# LHC_Power.net
KiCad netlist of a schematic drawn in Altium Designer
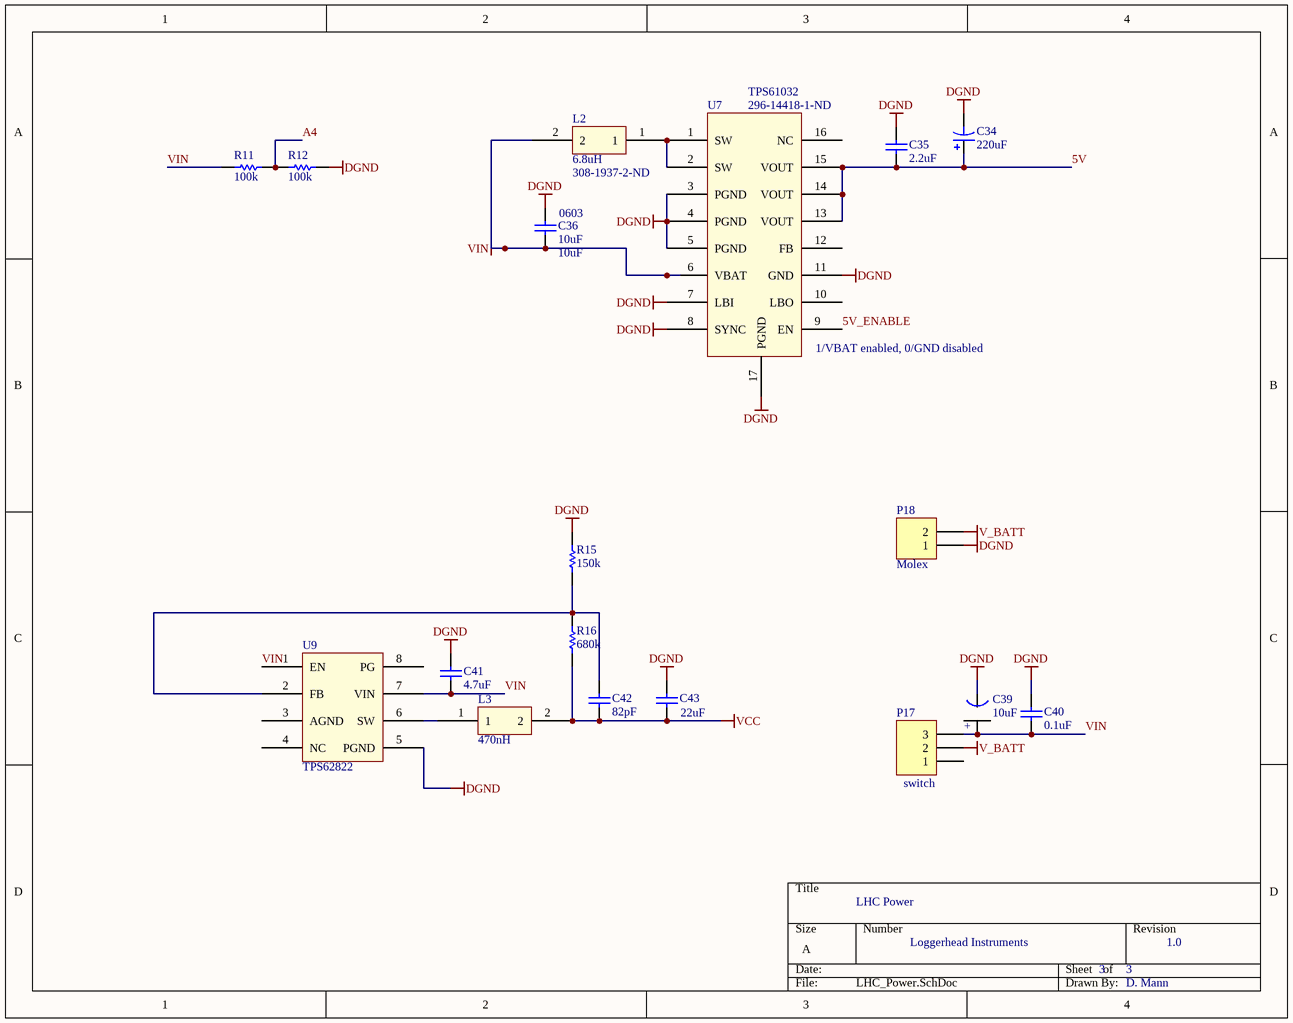
[diagram p0: LHC_Power.SchDoc]

(export (version "E")
  (design (tool "Eeschema 10.0.6"))
  (components
    (comp (ref "C34")
      (value "220uF")
      (footprint "X")
      (description "Solid Tantalum Chip Capacitor, Standard T495 Series - Low ESR, Surge Robust")
      (fields (field (name "PUBLISHER") "Altium Limited"))
      (libsource (lib "KEMET Chip Capacitor") (part "T495X"))
    )
    (comp (ref "C35")
      (value "2.2uF")
      (footprint "0402")
      (description "Ceramic Chip Capacitor - Standard")
      (fields (field (name "PUBLISHER") "Altium Limited"))
      (libsource (lib "KEMET Chip Capacitor") (part "C0402"))
    )
    (comp (ref "C36")
      (value "10uF")
      (footprint "0603")
      (description "Ceramic Chip Capacitor - 0603")
      (fields
        (field (name "PACKAGEREFERENCE") "0603")
        (field (name "ALTIUM_VALUE") "10uF")
        (field (name "PUBLISHER") "Altium Limited")
      )
      (libsource (lib "KEMET Chip Capacitor") (part "C0603"))
    )
    (comp (ref "C39") (value "10uF") (footprint "Tant0805") (libsource (lib "Loggerhead") (part "Tant0805")))
    (comp (ref "C40")
      (value "0.1uF")
      (footprint "0402")
      (description "Ceramic Chip Capacitor - Standard")
      (fields (field (name "PUBLISHER") "Altium Limited"))
      (libsource (lib "KEMET Chip Capacitor") (part "C0402"))
    )
    (comp (ref "C41")
      (value "4.7uF")
      (footprint "0603")
      (description "Ceramic Chip Capacitor - Standard")
      (fields (field (name "PUBLISHER") "Altium Limited"))
      (libsource (lib "KEMET Chip Capacitor") (part "C0603"))
    )
    (comp (ref "C42")
      (value "82pF")
      (footprint "0402")
      (description "Ceramic Chip Capacitor - Standard")
      (fields (field (name "PUBLISHER") "Altium Limited"))
      (libsource (lib "KEMET Chip Capacitor") (part "C0402"))
    )
    (comp (ref "C43")
      (value "22uF")
      (footprint "0603")
      (description "Ceramic Chip Capacitor - Standard")
      (fields (field (name "PUBLISHER") "Altium Limited"))
      (libsource (lib "KEMET Chip Capacitor") (part "C0603"))
    )
    (comp (ref "L2")
      (value "6.8uH")
      (footprint "Inductor - duplicate")
      (description "Sumida Inductor")
      (fields (field (name "SUPPLIER PART NUMBER 1") "308-1937-2-ND"))
      (libsource (lib "Loggerhead") (part "Inductor 6.8uH"))
    )
    (comp (ref "L3")
      (value "470nH")
      (footprint "Inductor_470NH")
      (libsource (lib "Loggerhead") (part "Inductor_470NH"))
    )
    (comp (ref "P17")
      (value "switch")
      (footprint "HDR1X3")
      (description "Header, 3-Pin")
      (fields (field (name "PUBLISHER") "Altium Limited"))
      (libsource (lib "Miscellaneous Connectors") (part "Header 3"))
    )
    (comp (ref "P18")
      (value "Molex")
      (footprint "HDR1X2")
      (description "Header, 2-Pin")
      (fields (field (name "PUBLISHER") "Altium Limited"))
      (libsource (lib "Miscellaneous Connectors") (part "Header 2"))
    )
    (comp (ref "R11")
      (value "100k")
      (footprint "3-0603")
      (fields (field (name "PUBLISHER") "Altium Limited"))
      (libsource (lib "Panasonic Resistor") (part "ERJ3RK"))
    )
    (comp (ref "R12")
      (value "100k")
      (footprint "3-0603")
      (fields (field (name "PUBLISHER") "Altium Limited"))
      (libsource (lib "Panasonic Resistor") (part "ERJ3RK"))
    )
    (comp (ref "R15")
      (value "150k")
      (footprint "3-0603")
      (fields (field (name "PUBLISHER") "Altium Limited"))
      (libsource (lib "Panasonic Resistor") (part "ERJ3RK"))
    )
    (comp (ref "R16")
      (value "680k")
      (footprint "3-0603")
      (fields (field (name "PUBLISHER") "Altium Limited"))
      (libsource (lib "Panasonic Resistor") (part "ERJ3RK"))
    )
    (comp (ref "U7")
      (value "TPS61032")
      (footprint "TPS6103x")
      (description "Boost converter")
      (fields (field (name "SUPPLIER PART NUMBER 2") "296-14418-1-ND"))
      (libsource (lib "Loggerhead") (part "TPS6103x"))
    )
    (comp (ref "U9")
      (value "TPS62822")
      (footprint "TPS62822_SOP8")
      (description "Step-down converter")
      (libsource (lib "Loggerhead") (part "TPS62822"))
    )
  )
  (nets
    (net (code "1") (name "/5V") (class "Default")
      (node (ref "C34") (pin "1") (pinfunction "1_1") (pintype "passive"))
      (node (ref "C35") (pin "1") (pinfunction "1_1") (pintype "passive"))
      (node (ref "U7") (pin "13") (pinfunction "VOUT_13") (pintype "passive"))
      (node (ref "U7") (pin "14") (pinfunction "VOUT_14") (pintype "passive"))
      (node (ref "U7") (pin "15") (pinfunction "VOUT_15") (pintype "passive"))
    )
    (net (code "2") (name "/5V_ENABLE") (class "Default")
      (node (ref "U7") (pin "9") (pinfunction "EN_9") (pintype "passive"))
    )
    (net (code "3") (name "/A4") (class "Default")
      (node (ref "R11") (pin "1") (pinfunction "1_1") (pintype "passive"))
      (node (ref "R12") (pin "2") (pinfunction "2_2") (pintype "passive"))
    )
    (net (code "4") (name "DGND") (class "Default")
      (node (ref "C34") (pin "2") (pinfunction "2_2") (pintype "passive"))
      (node (ref "C35") (pin "2") (pinfunction "2_2") (pintype "passive"))
      (node (ref "C36") (pin "1") (pinfunction "1_1") (pintype "passive"))
      (node (ref "C39") (pin "1") (pinfunction "GND_1") (pintype "passive"))
      (node (ref "C40") (pin "2") (pinfunction "2_2") (pintype "passive"))
      (node (ref "C41") (pin "1") (pinfunction "1_1") (pintype "passive"))
      (node (ref "C43") (pin "1") (pinfunction "1_1") (pintype "passive"))
      (node (ref "P18") (pin "1") (pinfunction "1_1") (pintype "passive"))
      (node (ref "R12") (pin "1") (pinfunction "1_1") (pintype "passive"))
      (node (ref "R15") (pin "2") (pinfunction "2_2") (pintype "passive"))
      (node (ref "U7") (pin "11") (pinfunction "GND_11") (pintype "passive"))
      (node (ref "U7") (pin "17") (pinfunction "PGND_17") (pintype "passive"))
      (node (ref "U7") (pin "3") (pinfunction "PGND_3") (pintype "passive"))
      (node (ref "U7") (pin "4") (pinfunction "PGND_4") (pintype "passive"))
      (node (ref "U7") (pin "5") (pinfunction "PGND_5") (pintype "passive"))
      (node (ref "U7") (pin "7") (pinfunction "LBI_7") (pintype "passive"))
      (node (ref "U7") (pin "8") (pinfunction "SYNC_8") (pintype "passive"))
      (node (ref "U9") (pin "5") (pinfunction "PGND_5") (pintype "passive"))
    )
    (net (code "5") (name "Net-(L2-Pad1)") (class "Default")
      (node (ref "L2") (pin "1") (pinfunction "1_1") (pintype "passive"))
      (node (ref "U7") (pin "1") (pinfunction "SW_1") (pintype "passive"))
      (node (ref "U7") (pin "2") (pinfunction "SW_2") (pintype "passive"))
    )
    (net (code "6") (name "Net-(U9-FB)") (class "Default")
      (node (ref "C42") (pin "2") (pinfunction "2_2") (pintype "passive"))
      (node (ref "R15") (pin "1") (pinfunction "1_1") (pintype "passive"))
      (node (ref "R16") (pin "2") (pinfunction "2_2") (pintype "passive"))
      (node (ref "U9") (pin "2") (pinfunction "FB_2") (pintype "passive"))
    )
    (net (code "7") (name "Net-(U9-SW)") (class "Default")
      (node (ref "L3") (pin "1") (pinfunction "1_1") (pintype "passive"))
      (node (ref "U9") (pin "6") (pinfunction "SW_6") (pintype "passive"))
    )
    (net (code "8") (name "VCC") (class "Default")
      (node (ref "C42") (pin "1") (pinfunction "1_1") (pintype "passive"))
      (node (ref "C43") (pin "2") (pinfunction "2_2") (pintype "passive"))
      (node (ref "L3") (pin "2") (pinfunction "2_2") (pintype "passive"))
      (node (ref "R16") (pin "1") (pinfunction "1_1") (pintype "passive"))
    )
    (net (code "9") (name "VIN") (class "Default")
      (node (ref "C36") (pin "2") (pinfunction "2_2") (pintype "passive"))
      (node (ref "C39") (pin "2") (pinfunction "+_2") (pintype "passive"))
      (node (ref "C40") (pin "1") (pinfunction "1_1") (pintype "passive"))
      (node (ref "C41") (pin "2") (pinfunction "2_2") (pintype "passive"))
      (node (ref "L2") (pin "2") (pinfunction "2_2") (pintype "passive"))
      (node (ref "P17") (pin "3") (pinfunction "3_3") (pintype "passive"))
      (node (ref "R11") (pin "2") (pinfunction "2_2") (pintype "passive"))
      (node (ref "U7") (pin "6") (pinfunction "VBAT_6") (pintype "passive"))
      (node (ref "U9") (pin "1") (pinfunction "EN_1") (pintype "passive"))
      (node (ref "U9") (pin "7") (pinfunction "VIN_7") (pintype "passive"))
    )
    (net (code "10") (name "V_BATT") (class "Default")
      (node (ref "P17") (pin "2") (pinfunction "2_2") (pintype "passive"))
      (node (ref "P18") (pin "2") (pinfunction "2_2") (pintype "passive"))
    )
    (net (code "11") (name "unconnected-(P17-Pad1)") (class "Default")
      (node (ref "P17") (pin "1") (pinfunction "1_1") (pintype "passive"))
    )
    (net (code "12") (name "unconnected-(U7-FB-Pad12)") (class "Default")
      (node (ref "U7") (pin "12") (pinfunction "FB_12") (pintype "passive"))
    )
    (net (code "13") (name "unconnected-(U7-LBO-Pad10)") (class "Default")
      (node (ref "U7") (pin "10") (pinfunction "LBO_10") (pintype "passive"))
    )
    (net (code "14") (name "unconnected-(U7-NC-Pad16)") (class "Default")
      (node (ref "U7") (pin "16") (pinfunction "NC_16") (pintype "passive"))
    )
    (net (code "15") (name "unconnected-(U9-AGND-Pad3)") (class "Default")
      (node (ref "U9") (pin "3") (pinfunction "AGND_3") (pintype "passive"))
    )
    (net (code "16") (name "unconnected-(U9-NC-Pad4)") (class "Default")
      (node (ref "U9") (pin "4") (pinfunction "NC_4") (pintype "passive"))
    )
    (net (code "17") (name "unconnected-(U9-PG-Pad8)") (class "Default")
      (node (ref "U9") (pin "8") (pinfunction "PG_8") (pintype "passive"))
    )
  )
)
